# LvlTranslate.net
KiCad netlist of a schematic drawn in Altium Designer
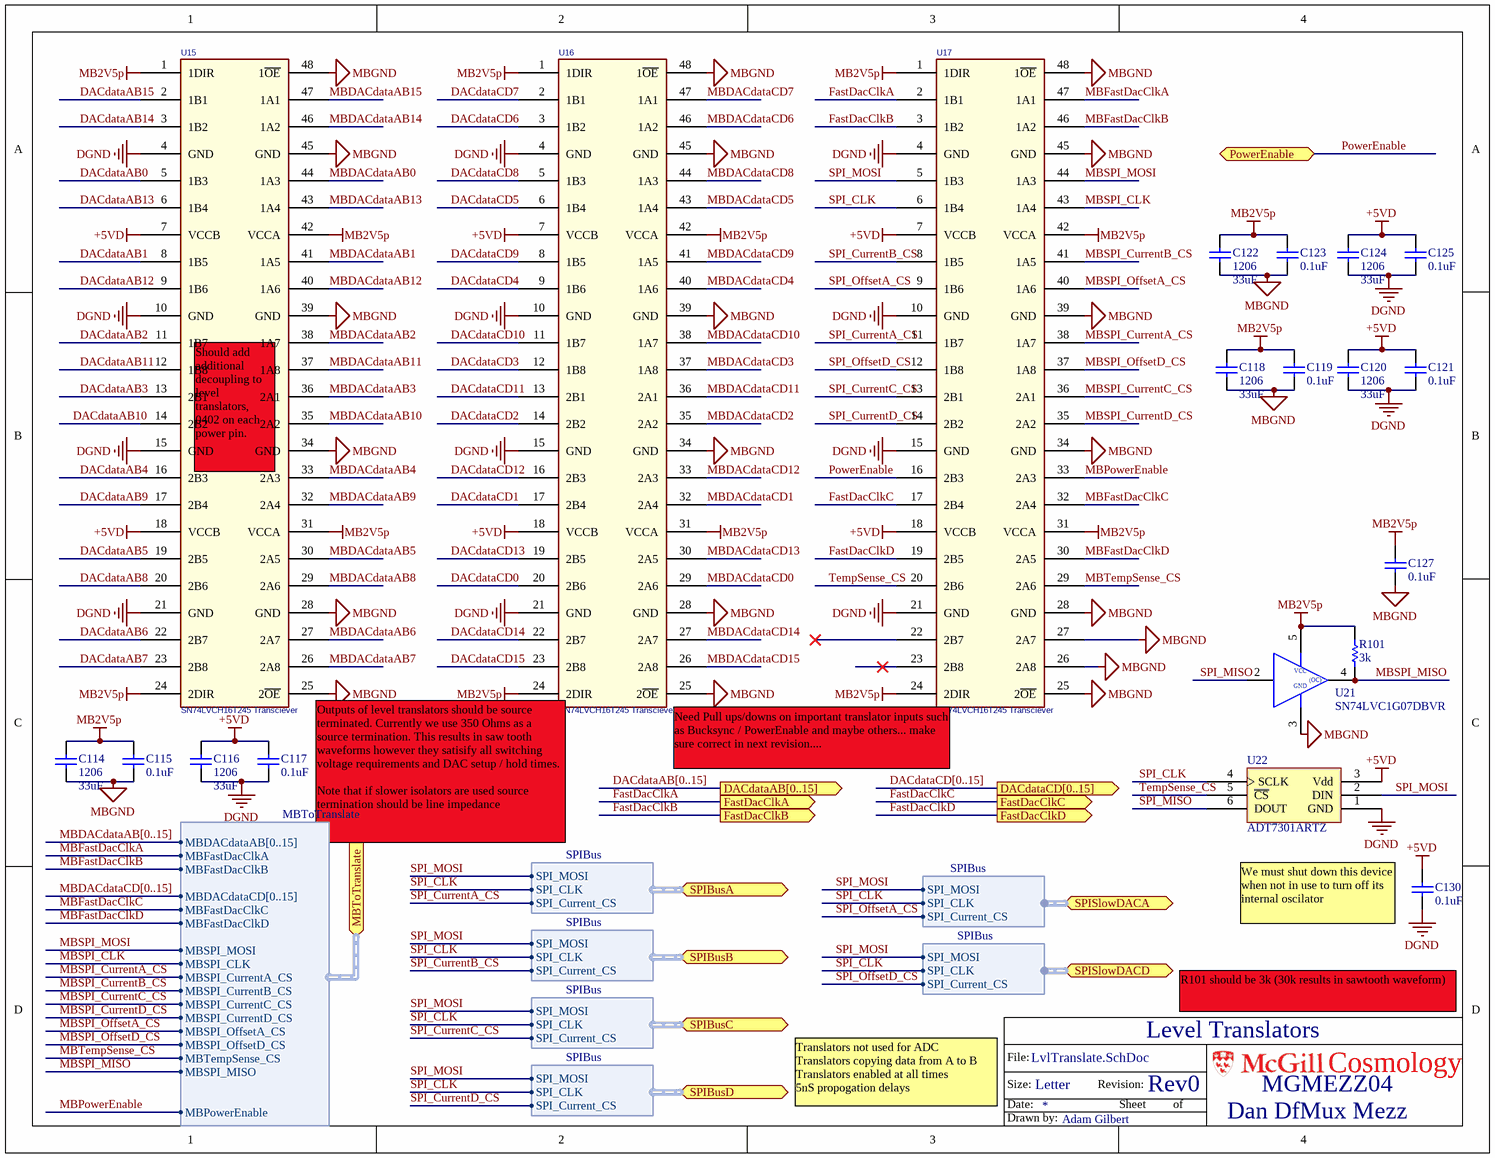
[diagram p0: LvlTranslate.SchDoc]

(export (version "E")
  (design (tool "Eeschema 10.0.6"))
  (components
    (comp (ref "C114")
      (value "33uF")
      (footprint "1206")
      (description "Capacitor, Ceramic, 1210")
      (fields
        (field (name "MANUFACTURER") "TDK Corporation")
        (field (name "MANUFACTURERS PART NUMBER") "C3216X5R1E336M")
      )
      (libsource (lib "MGMEZZ04") (part "CAP 1210"))
    )
    (comp (ref "C115")
      (value "0.1uF")
      (footprint "0603")
      (description "Capacitor, Ceramic, 0603")
      (fields (field (name "MANUFACTURER") "Generic"))
      (libsource (lib "MGMEZZ04") (part "CAP 0603"))
    )
    (comp (ref "C116")
      (value "33uF")
      (footprint "1206")
      (description "Capacitor, Ceramic, 1210")
      (fields
        (field (name "MANUFACTURER") "TDK Corporation")
        (field (name "MANUFACTURERS PART NUMBER") "C3216X5R1E336M")
      )
      (libsource (lib "MGMEZZ04") (part "CAP 1210"))
    )
    (comp (ref "C117")
      (value "0.1uF")
      (footprint "0603")
      (description "Capacitor, Ceramic, 0603")
      (fields (field (name "MANUFACTURER") "Generic"))
      (libsource (lib "MGMEZZ04") (part "CAP 0603"))
    )
    (comp (ref "C118")
      (value "33uF")
      (footprint "1206")
      (description "Capacitor, Ceramic, 1210")
      (fields
        (field (name "MANUFACTURER") "TDK Corporation")
        (field (name "MANUFACTURERS PART NUMBER") "C3216X5R1E336M")
      )
      (libsource (lib "MGMEZZ04") (part "CAP 1210"))
    )
    (comp (ref "C119")
      (value "0.1uF")
      (footprint "0603")
      (description "Capacitor, Ceramic, 0603")
      (fields (field (name "MANUFACTURER") "Generic"))
      (libsource (lib "MGMEZZ04") (part "CAP 0603"))
    )
    (comp (ref "C120")
      (value "33uF")
      (footprint "1206")
      (description "Capacitor, Ceramic, 1210")
      (fields
        (field (name "MANUFACTURER") "TDK Corporation")
        (field (name "MANUFACTURERS PART NUMBER") "C3216X5R1E336M")
      )
      (libsource (lib "MGMEZZ04") (part "CAP 1210"))
    )
    (comp (ref "C121")
      (value "0.1uF")
      (footprint "0603")
      (description "Capacitor, Ceramic, 0603")
      (fields (field (name "MANUFACTURER") "Generic"))
      (libsource (lib "MGMEZZ04") (part "CAP 0603"))
    )
    (comp (ref "C122")
      (value "33uF")
      (footprint "1206")
      (description "Capacitor, Ceramic, 1210")
      (fields
        (field (name "MANUFACTURER") "TDK Corporation")
        (field (name "MANUFACTURERS PART NUMBER") "C3216X5R1E336M")
      )
      (libsource (lib "MGMEZZ04") (part "CAP 1210"))
    )
    (comp (ref "C123")
      (value "0.1uF")
      (footprint "0603")
      (description "Capacitor, Ceramic, 0603")
      (fields (field (name "MANUFACTURER") "Generic"))
      (libsource (lib "MGMEZZ04") (part "CAP 0603"))
    )
    (comp (ref "C124")
      (value "33uF")
      (footprint "1206")
      (description "Capacitor, Ceramic, 1210")
      (fields
        (field (name "MANUFACTURER") "TDK Corporation")
        (field (name "MANUFACTURERS PART NUMBER") "C3216X5R1E336M")
      )
      (libsource (lib "MGMEZZ04") (part "CAP 1210"))
    )
    (comp (ref "C125")
      (value "0.1uF")
      (footprint "0603")
      (description "Capacitor, Ceramic, 0603")
      (fields (field (name "MANUFACTURER") "Generic"))
      (libsource (lib "MGMEZZ04") (part "CAP 0603"))
    )
    (comp (ref "C127")
      (value "0.1uF")
      (footprint "0603")
      (description "Capacitor, Ceramic, 0603")
      (fields (field (name "MANUFACTURER") "Generic"))
      (libsource (lib "MGMEZZ04") (part "CAP 0603"))
    )
    (comp (ref "C130")
      (value "0.1uF")
      (footprint "0603")
      (description "Capacitor, Ceramic, 0603")
      (fields (field (name "MANUFACTURER") "Generic"))
      (libsource (lib "MGMEZZ04") (part "CAP 0603"))
    )
    (comp (ref "R101")
      (value "3k")
      (footprint "0603")
      (description "Resistor")
      (fields (field (name "MANUFACTURER") "Generic"))
      (libsource (lib "MGMEZZ04") (part "RES 0603"))
    )
    (comp (ref "U15")
      (value "SN74LVCH16T245 Transciever")
      (footprint "TSSOP48-0.5mmpitch")
      (fields
        (field (name "MANUFACTURER") "Texas Instruments")
        (field (name "MANUFACTURERS PART NUMBER") "SN74LVCH16T245")
      )
      (libsource (lib "MGMEZZ04") (part "SN74LVCH16T245 Transciever"))
    )
    (comp (ref "U16")
      (value "SN74LVCH16T245 Transciever")
      (footprint "TSSOP48-0.5mmpitch")
      (fields
        (field (name "MANUFACTURER") "Texas Instruments")
        (field (name "MANUFACTURERS PART NUMBER") "SN74LVCH16T245")
      )
      (libsource (lib "MGMEZZ04") (part "SN74LVCH16T245 Transciever"))
    )
    (comp (ref "U17")
      (value "SN74LVCH16T245 Transciever")
      (footprint "TSSOP48-0.5mmpitch")
      (fields
        (field (name "MANUFACTURER") "Texas Instruments")
        (field (name "MANUFACTURERS PART NUMBER") "SN74LVCH16T245")
      )
      (libsource (lib "MGMEZZ04") (part "SN74LVCH16T245 Transciever"))
    )
    (comp (ref "U21")
      (value "74LVC1G07")
      (footprint "SOT23-5")
      (description "Single  NON-INVERTING BUFFER, Open Drain")
      (fields
        (field (name "MANUFACTURER") "Texas Instruments")
        (field (name "MANUFACTURERS PART NUMBER") "SN74LVC1G07DBVR")
      )
      (libsource (lib "MGMEZZ04") (part "74LVC1G07"))
    )
    (comp (ref "U22")
      (value "ADT7301ARTZ")
      (footprint "SOT23-6")
      (description "Digital Temperature Sensor, 13-Bit, +/-1 Degree Accurate")
      (fields (field (name "MANUFACTURER") "Analog Devices"))
      (libsource (lib "ADCMezz3") (part "ADT7301"))
    )
  )
  (nets
    (net (code "3") (name "+5VD") (class "Default")
      (node (ref "C116") (pin "1") (pinfunction "1_1") (pintype "passive"))
      (node (ref "C117") (pin "1") (pinfunction "1_1") (pintype "passive"))
      (node (ref "C120") (pin "1") (pinfunction "1_1") (pintype "passive"))
      (node (ref "C121") (pin "1") (pinfunction "1_1") (pintype "passive"))
      (node (ref "C124") (pin "1") (pinfunction "1_1") (pintype "passive"))
      (node (ref "C125") (pin "1") (pinfunction "1_1") (pintype "passive"))
      (node (ref "C130") (pin "1") (pinfunction "1_1") (pintype "passive"))
      (node (ref "U15") (pin "18") (pinfunction "VCCB_18") (pintype "passive"))
      (node (ref "U15") (pin "7") (pinfunction "VCCB_7") (pintype "passive"))
      (node (ref "U16") (pin "18") (pinfunction "VCCB_18") (pintype "passive"))
      (node (ref "U16") (pin "7") (pinfunction "VCCB_7") (pintype "passive"))
      (node (ref "U17") (pin "18") (pinfunction "VCCB_18") (pintype "passive"))
      (node (ref "U17") (pin "7") (pinfunction "VCCB_7") (pintype "passive"))
      (node (ref "U22") (pin "3") (pinfunction "Vdd_3") (pintype "power_in"))
    )
    (net (code "4") (name "/DACdataAB0") (class "Default")
      (node (ref "U15") (pin "5") (pinfunction "1B3_5") (pintype "passive"))
    )
    (net (code "5") (name "/DACdataAB1") (class "Default")
      (node (ref "U15") (pin "8") (pinfunction "1B5_8") (pintype "passive"))
    )
    (net (code "6") (name "/DACdataAB2") (class "Default")
      (node (ref "U15") (pin "11") (pinfunction "1B7_11") (pintype "passive"))
    )
    (net (code "7") (name "/DACdataAB3") (class "Default")
      (node (ref "U15") (pin "13") (pinfunction "2B1_13") (pintype "passive"))
    )
    (net (code "8") (name "/DACdataAB4") (class "Default")
      (node (ref "U15") (pin "16") (pinfunction "2B3_16") (pintype "passive"))
    )
    (net (code "9") (name "/DACdataAB5") (class "Default")
      (node (ref "U15") (pin "19") (pinfunction "2B5_19") (pintype "passive"))
    )
    (net (code "10") (name "/DACdataAB6") (class "Default")
      (node (ref "U15") (pin "22") (pinfunction "2B7_22") (pintype "passive"))
    )
    (net (code "11") (name "/DACdataAB7") (class "Default")
      (node (ref "U15") (pin "23") (pinfunction "2B8_23") (pintype "passive"))
    )
    (net (code "12") (name "/DACdataAB8") (class "Default")
      (node (ref "U15") (pin "20") (pinfunction "2B6_20") (pintype "passive"))
    )
    (net (code "13") (name "/DACdataAB9") (class "Default")
      (node (ref "U15") (pin "17") (pinfunction "2B4_17") (pintype "passive"))
    )
    (net (code "14") (name "/DACdataAB10") (class "Default")
      (node (ref "U15") (pin "14") (pinfunction "2B2_14") (pintype "passive"))
    )
    (net (code "15") (name "/DACdataAB11") (class "Default")
      (node (ref "U15") (pin "12") (pinfunction "1B8_12") (pintype "passive"))
    )
    (net (code "16") (name "/DACdataAB12") (class "Default")
      (node (ref "U15") (pin "9") (pinfunction "1B6_9") (pintype "passive"))
    )
    (net (code "17") (name "/DACdataAB13") (class "Default")
      (node (ref "U15") (pin "6") (pinfunction "1B4_6") (pintype "passive"))
    )
    (net (code "18") (name "/DACdataAB14") (class "Default")
      (node (ref "U15") (pin "3") (pinfunction "1B2_3") (pintype "passive"))
    )
    (net (code "19") (name "/DACdataAB15") (class "Default")
      (node (ref "U15") (pin "2") (pinfunction "1B1_2") (pintype "passive"))
    )
    (net (code "21") (name "/DACdataCD0") (class "Default")
      (node (ref "U16") (pin "20") (pinfunction "2B6_20") (pintype "passive"))
    )
    (net (code "22") (name "/DACdataCD1") (class "Default")
      (node (ref "U16") (pin "17") (pinfunction "2B4_17") (pintype "passive"))
    )
    (net (code "23") (name "/DACdataCD2") (class "Default")
      (node (ref "U16") (pin "14") (pinfunction "2B2_14") (pintype "passive"))
    )
    (net (code "24") (name "/DACdataCD3") (class "Default")
      (node (ref "U16") (pin "12") (pinfunction "1B8_12") (pintype "passive"))
    )
    (net (code "25") (name "/DACdataCD4") (class "Default")
      (node (ref "U16") (pin "9") (pinfunction "1B6_9") (pintype "passive"))
    )
    (net (code "26") (name "/DACdataCD5") (class "Default")
      (node (ref "U16") (pin "6") (pinfunction "1B4_6") (pintype "passive"))
    )
    (net (code "27") (name "/DACdataCD6") (class "Default")
      (node (ref "U16") (pin "3") (pinfunction "1B2_3") (pintype "passive"))
    )
    (net (code "28") (name "/DACdataCD7") (class "Default")
      (node (ref "U16") (pin "2") (pinfunction "1B1_2") (pintype "passive"))
    )
    (net (code "29") (name "/DACdataCD8") (class "Default")
      (node (ref "U16") (pin "5") (pinfunction "1B3_5") (pintype "passive"))
    )
    (net (code "30") (name "/DACdataCD9") (class "Default")
      (node (ref "U16") (pin "8") (pinfunction "1B5_8") (pintype "passive"))
    )
    (net (code "31") (name "/DACdataCD10") (class "Default")
      (node (ref "U16") (pin "11") (pinfunction "1B7_11") (pintype "passive"))
    )
    (net (code "32") (name "/DACdataCD11") (class "Default")
      (node (ref "U16") (pin "13") (pinfunction "2B1_13") (pintype "passive"))
    )
    (net (code "33") (name "/DACdataCD12") (class "Default")
      (node (ref "U16") (pin "16") (pinfunction "2B3_16") (pintype "passive"))
    )
    (net (code "34") (name "/DACdataCD13") (class "Default")
      (node (ref "U16") (pin "19") (pinfunction "2B5_19") (pintype "passive"))
    )
    (net (code "35") (name "/DACdataCD14") (class "Default")
      (node (ref "U16") (pin "22") (pinfunction "2B7_22") (pintype "passive"))
    )
    (net (code "36") (name "/DACdataCD15") (class "Default")
      (node (ref "U16") (pin "23") (pinfunction "2B8_23") (pintype "passive"))
    )
    (net (code "38") (name "/FastDacClkA") (class "Default")
      (node (ref "U17") (pin "2") (pinfunction "1B1_2") (pintype "passive"))
    )
    (net (code "39") (name "/FastDacClkB") (class "Default")
      (node (ref "U17") (pin "3") (pinfunction "1B2_3") (pintype "passive"))
    )
    (net (code "40") (name "/FastDacClkC") (class "Default")
      (node (ref "U17") (pin "17") (pinfunction "2B4_17") (pintype "passive"))
    )
    (net (code "41") (name "/FastDacClkD") (class "Default")
      (node (ref "U17") (pin "19") (pinfunction "2B5_19") (pintype "passive"))
    )
    (net (code "42") (name "/MBDACdataAB0") (class "Default")
      (node (ref "U15") (pin "44") (pinfunction "1A3_44") (pintype "passive"))
    )
    (net (code "43") (name "/MBDACdataAB1") (class "Default")
      (node (ref "U15") (pin "41") (pinfunction "1A5_41") (pintype "passive"))
    )
    (net (code "44") (name "/MBDACdataAB2") (class "Default")
      (node (ref "U15") (pin "38") (pinfunction "1A7_38") (pintype "passive"))
    )
    (net (code "45") (name "/MBDACdataAB3") (class "Default")
      (node (ref "U15") (pin "36") (pinfunction "2A1_36") (pintype "passive"))
    )
    (net (code "46") (name "/MBDACdataAB4") (class "Default")
      (node (ref "U15") (pin "33") (pinfunction "2A3_33") (pintype "passive"))
    )
    (net (code "47") (name "/MBDACdataAB5") (class "Default")
      (node (ref "U15") (pin "30") (pinfunction "2A5_30") (pintype "passive"))
    )
    (net (code "48") (name "/MBDACdataAB6") (class "Default")
      (node (ref "U15") (pin "27") (pinfunction "2A7_27") (pintype "passive"))
    )
    (net (code "49") (name "/MBDACdataAB7") (class "Default")
      (node (ref "U15") (pin "26") (pinfunction "2A8_26") (pintype "passive"))
    )
    (net (code "50") (name "/MBDACdataAB8") (class "Default")
      (node (ref "U15") (pin "29") (pinfunction "2A6_29") (pintype "passive"))
    )
    (net (code "51") (name "/MBDACdataAB9") (class "Default")
      (node (ref "U15") (pin "32") (pinfunction "2A4_32") (pintype "passive"))
    )
    (net (code "52") (name "/MBDACdataAB10") (class "Default")
      (node (ref "U15") (pin "35") (pinfunction "2A2_35") (pintype "passive"))
    )
    (net (code "53") (name "/MBDACdataAB11") (class "Default")
      (node (ref "U15") (pin "37") (pinfunction "1A8_37") (pintype "passive"))
    )
    (net (code "54") (name "/MBDACdataAB12") (class "Default")
      (node (ref "U15") (pin "40") (pinfunction "1A6_40") (pintype "passive"))
    )
    (net (code "55") (name "/MBDACdataAB13") (class "Default")
      (node (ref "U15") (pin "43") (pinfunction "1A4_43") (pintype "passive"))
    )
    (net (code "56") (name "/MBDACdataAB14") (class "Default")
      (node (ref "U15") (pin "46") (pinfunction "1A2_46") (pintype "passive"))
    )
    (net (code "57") (name "/MBDACdataAB15") (class "Default")
      (node (ref "U15") (pin "47") (pinfunction "1A1_47") (pintype "passive"))
    )
    (net (code "59") (name "/MBDACdataCD0") (class "Default")
      (node (ref "U16") (pin "29") (pinfunction "2A6_29") (pintype "passive"))
    )
    (net (code "60") (name "/MBDACdataCD1") (class "Default")
      (node (ref "U16") (pin "32") (pinfunction "2A4_32") (pintype "passive"))
    )
    (net (code "61") (name "/MBDACdataCD2") (class "Default")
      (node (ref "U16") (pin "35") (pinfunction "2A2_35") (pintype "passive"))
    )
    (net (code "62") (name "/MBDACdataCD3") (class "Default")
      (node (ref "U16") (pin "37") (pinfunction "1A8_37") (pintype "passive"))
    )
    (net (code "63") (name "/MBDACdataCD4") (class "Default")
      (node (ref "U16") (pin "40") (pinfunction "1A6_40") (pintype "passive"))
    )
    (net (code "64") (name "/MBDACdataCD5") (class "Default")
      (node (ref "U16") (pin "43") (pinfunction "1A4_43") (pintype "passive"))
    )
    (net (code "65") (name "/MBDACdataCD6") (class "Default")
      (node (ref "U16") (pin "46") (pinfunction "1A2_46") (pintype "passive"))
    )
    (net (code "66") (name "/MBDACdataCD7") (class "Default")
      (node (ref "U16") (pin "47") (pinfunction "1A1_47") (pintype "passive"))
    )
    (net (code "67") (name "/MBDACdataCD8") (class "Default")
      (node (ref "U16") (pin "44") (pinfunction "1A3_44") (pintype "passive"))
    )
    (net (code "68") (name "/MBDACdataCD9") (class "Default")
      (node (ref "U16") (pin "41") (pinfunction "1A5_41") (pintype "passive"))
    )
    (net (code "69") (name "/MBDACdataCD10") (class "Default")
      (node (ref "U16") (pin "38") (pinfunction "1A7_38") (pintype "passive"))
    )
    (net (code "70") (name "/MBDACdataCD11") (class "Default")
      (node (ref "U16") (pin "36") (pinfunction "2A1_36") (pintype "passive"))
    )
    (net (code "71") (name "/MBDACdataCD12") (class "Default")
      (node (ref "U16") (pin "33") (pinfunction "2A3_33") (pintype "passive"))
    )
    (net (code "72") (name "/MBDACdataCD13") (class "Default")
      (node (ref "U16") (pin "30") (pinfunction "2A5_30") (pintype "passive"))
    )
    (net (code "73") (name "/MBDACdataCD14") (class "Default")
      (node (ref "U16") (pin "27") (pinfunction "2A7_27") (pintype "passive"))
    )
    (net (code "74") (name "/MBDACdataCD15") (class "Default")
      (node (ref "U16") (pin "26") (pinfunction "2A8_26") (pintype "passive"))
    )
    (net (code "76") (name "/MBFastDacClkA") (class "Default")
      (node (ref "U17") (pin "47") (pinfunction "1A1_47") (pintype "passive"))
    )
    (net (code "77") (name "/MBFastDacClkB") (class "Default")
      (node (ref "U17") (pin "46") (pinfunction "1A2_46") (pintype "passive"))
    )
    (net (code "78") (name "/MBFastDacClkC") (class "Default")
      (node (ref "U17") (pin "32") (pinfunction "2A4_32") (pintype "passive"))
    )
    (net (code "79") (name "/MBFastDacClkD") (class "Default")
      (node (ref "U17") (pin "30") (pinfunction "2A5_30") (pintype "passive"))
    )
    (net (code "80") (name "/MBPowerEnable") (class "Default")
      (node (ref "U17") (pin "33") (pinfunction "2A3_33") (pintype "passive"))
    )
    (net (code "81") (name "/MBSPI_CLK") (class "Default")
      (node (ref "U17") (pin "43") (pinfunction "1A4_43") (pintype "passive"))
    )
    (net (code "82") (name "/MBSPI_CurrentA_CS") (class "Default")
      (node (ref "U17") (pin "38") (pinfunction "1A7_38") (pintype "passive"))
    )
    (net (code "83") (name "/MBSPI_CurrentB_CS") (class "Default")
      (node (ref "U17") (pin "41") (pinfunction "1A5_41") (pintype "passive"))
    )
    (net (code "84") (name "/MBSPI_CurrentC_CS") (class "Default")
      (node (ref "U17") (pin "36") (pinfunction "2A1_36") (pintype "passive"))
    )
    (net (code "85") (name "/MBSPI_CurrentD_CS") (class "Default")
      (node (ref "U17") (pin "35") (pinfunction "2A2_35") (pintype "passive"))
    )
    (net (code "86") (name "/MBSPI_MISO") (class "Default")
      (node (ref "R101") (pin "1") (pinfunction "1_1") (pintype "passive"))
      (node (ref "U21") (pin "4") (pinfunction "Y_4") (pintype "passive"))
    )
    (net (code "87") (name "/MBSPI_MOSI") (class "Default")
      (node (ref "U17") (pin "44") (pinfunction "1A3_44") (pintype "passive"))
    )
    (net (code "88") (name "/MBSPI_OffsetA_CS") (class "Default")
      (node (ref "U17") (pin "40") (pinfunction "1A6_40") (pintype "passive"))
    )
    (net (code "89") (name "/MBSPI_OffsetD_CS") (class "Default")
      (node (ref "U17") (pin "37") (pinfunction "1A8_37") (pintype "passive"))
    )
    (net (code "90") (name "/MBTempSense_CS") (class "Default")
      (node (ref "U17") (pin "29") (pinfunction "2A6_29") (pintype "passive"))
    )
    (net (code "91") (name "/PowerEnable") (class "Default")
      (node (ref "U17") (pin "16") (pinfunction "2B3_16") (pintype "passive"))
    )
    (net (code "92") (name "/SPI_CLK") (class "Default")
      (node (ref "U17") (pin "6") (pinfunction "1B4_6") (pintype "passive"))
      (node (ref "U22") (pin "4") (pinfunction "SCLK_4") (pintype "passive"))
    )
    (net (code "93") (name "/SPI_CurrentA_CS") (class "Default")
      (node (ref "U17") (pin "11") (pinfunction "1B7_11") (pintype "passive"))
    )
    (net (code "94") (name "/SPI_CurrentB_CS") (class "Default")
      (node (ref "U17") (pin "8") (pinfunction "1B5_8") (pintype "passive"))
    )
    (net (code "95") (name "/SPI_CurrentC_CS") (class "Default")
      (node (ref "U17") (pin "13") (pinfunction "2B1_13") (pintype "passive"))
    )
    (net (code "96") (name "/SPI_CurrentD_CS") (class "Default")
      (node (ref "U17") (pin "14") (pinfunction "2B2_14") (pintype "passive"))
    )
    (net (code "97") (name "/SPI_MISO") (class "Default")
      (node (ref "U21") (pin "2") (pinfunction "A_2") (pintype "passive"))
      (node (ref "U22") (pin "6") (pinfunction "DOUT_6") (pintype "passive"))
    )
    (net (code "98") (name "/SPI_MOSI") (class "Default")
      (node (ref "U17") (pin "5") (pinfunction "1B3_5") (pintype "passive"))
      (node (ref "U22") (pin "2") (pinfunction "DIN_2") (pintype "passive"))
    )
    (net (code "99") (name "/SPI_OffsetA_CS") (class "Default")
      (node (ref "U17") (pin "9") (pinfunction "1B6_9") (pintype "passive"))
    )
    (net (code "100") (name "/SPI_OffsetD_CS") (class "Default")
      (node (ref "U17") (pin "12") (pinfunction "1B8_12") (pintype "passive"))
    )
    (net (code "101") (name "/TempSense_CS") (class "Default")
      (node (ref "U17") (pin "20") (pinfunction "2B6_20") (pintype "passive"))
      (node (ref "U22") (pin "5") (pinfunction "~{CS}_5") (pintype "passive"))
    )
    (net (code "104") (name "DGND") (class "Default")
      (node (ref "C116") (pin "2") (pinfunction "2_2") (pintype "passive"))
      (node (ref "C117") (pin "2") (pinfunction "2_2") (pintype "passive"))
      (node (ref "C120") (pin "2") (pinfunction "2_2") (pintype "passive"))
      (node (ref "C121") (pin "2") (pinfunction "2_2") (pintype "passive"))
      (node (ref "C124") (pin "2") (pinfunction "2_2") (pintype "passive"))
      (node (ref "C125") (pin "2") (pinfunction "2_2") (pintype "passive"))
      (node (ref "C130") (pin "2") (pinfunction "2_2") (pintype "passive"))
      (node (ref "U15") (pin "10") (pinfunction "GND_10") (pintype "passive"))
      (node (ref "U15") (pin "15") (pinfunction "GND_15") (pintype "passive"))
      (node (ref "U15") (pin "21") (pinfunction "GND_21") (pintype "passive"))
      (node (ref "U15") (pin "4") (pinfunction "GND_4") (pintype "passive"))
      (node (ref "U16") (pin "10") (pinfunction "GND_10") (pintype "passive"))
      (node (ref "U16") (pin "15") (pinfunction "GND_15") (pintype "passive"))
      (node (ref "U16") (pin "21") (pinfunction "GND_21") (pintype "passive"))
      (node (ref "U16") (pin "4") (pinfunction "GND_4") (pintype "passive"))
      (node (ref "U17") (pin "10") (pinfunction "GND_10") (pintype "passive"))
      (node (ref "U17") (pin "15") (pinfunction "GND_15") (pintype "passive"))
      (node (ref "U17") (pin "21") (pinfunction "GND_21") (pintype "passive"))
      (node (ref "U17") (pin "4") (pinfunction "GND_4") (pintype "passive"))
      (node (ref "U22") (pin "1") (pinfunction "GND_1") (pintype "power_in"))
    )
    (net (code "105") (name "MB2V5p") (class "Default")
      (node (ref "C114") (pin "1") (pinfunction "1_1") (pintype "passive"))
      (node (ref "C115") (pin "1") (pinfunction "1_1") (pintype "passive"))
      (node (ref "C118") (pin "1") (pinfunction "1_1") (pintype "passive"))
      (node (ref "C119") (pin "1") (pinfunction "1_1") (pintype "passive"))
      (node (ref "C122") (pin "1") (pinfunction "1_1") (pintype "passive"))
      (node (ref "C123") (pin "1") (pinfunction "1_1") (pintype "passive"))
      (node (ref "C127") (pin "1") (pinfunction "1_1") (pintype "passive"))
      (node (ref "R101") (pin "2") (pinfunction "2_2") (pintype "passive"))
      (node (ref "U15") (pin "1") (pinfunction "1DIR_1") (pintype "passive"))
      (node (ref "U15") (pin "24") (pinfunction "2DIR_24") (pintype "passive"))
      (node (ref "U15") (pin "31") (pinfunction "VCCA_31") (pintype "passive"))
      (node (ref "U15") (pin "42") (pinfunction "VCCA_42") (pintype "passive"))
      (node (ref "U16") (pin "1") (pinfunction "1DIR_1") (pintype "passive"))
      (node (ref "U16") (pin "24") (pinfunction "2DIR_24") (pintype "passive"))
      (node (ref "U16") (pin "31") (pinfunction "VCCA_31") (pintype "passive"))
      (node (ref "U16") (pin "42") (pinfunction "VCCA_42") (pintype "passive"))
      (node (ref "U17") (pin "1") (pinfunction "1DIR_1") (pintype "passive"))
      (node (ref "U17") (pin "24") (pinfunction "2DIR_24") (pintype "passive"))
      (node (ref "U17") (pin "31") (pinfunction "VCCA_31") (pintype "passive"))
      (node (ref "U17") (pin "42") (pinfunction "VCCA_42") (pintype "passive"))
      (node (ref "U21") (pin "5") (pinfunction "Vcc_5") (pintype "power_in"))
    )
    (net (code "106") (name "MBGND") (class "Default")
      (node (ref "C114") (pin "2") (pinfunction "2_2") (pintype "passive"))
      (node (ref "C115") (pin "2") (pinfunction "2_2") (pintype "passive"))
      (node (ref "C118") (pin "2") (pinfunction "2_2") (pintype "passive"))
      (node (ref "C119") (pin "2") (pinfunction "2_2") (pintype "passive"))
      (node (ref "C122") (pin "2") (pinfunction "2_2") (pintype "passive"))
      (node (ref "C123") (pin "2") (pinfunction "2_2") (pintype "passive"))
      (node (ref "C127") (pin "2") (pinfunction "2_2") (pintype "passive"))
      (node (ref "U15") (pin "25") (pinfunction "2~{OE}_25") (pintype "passive"))
      (node (ref "U15") (pin "28") (pinfunction "GND_28") (pintype "passive"))
      (node (ref "U15") (pin "34") (pinfunction "GND_34") (pintype "passive"))
      (node (ref "U15") (pin "39") (pinfunction "GND_39") (pintype "passive"))
      (node (ref "U15") (pin "45") (pinfunction "GND_45") (pintype "passive"))
      (node (ref "U15") (pin "48") (pinfunction "1~{OE}_48") (pintype "passive"))
      (node (ref "U16") (pin "25") (pinfunction "2~{OE}_25") (pintype "passive"))
      (node (ref "U16") (pin "28") (pinfunction "GND_28") (pintype "passive"))
      (node (ref "U16") (pin "34") (pinfunction "GND_34") (pintype "passive"))
      (node (ref "U16") (pin "39") (pinfunction "GND_39") (pintype "passive"))
      (node (ref "U16") (pin "45") (pinfunction "GND_45") (pintype "passive"))
      (node (ref "U16") (pin "48") (pinfunction "1~{OE}_48") (pintype "passive"))
      (node (ref "U17") (pin "25") (pinfunction "2~{OE}_25") (pintype "passive"))
      (node (ref "U17") (pin "26") (pinfunction "2A8_26") (pintype "passive"))
      (node (ref "U17") (pin "27") (pinfunction "2A7_27") (pintype "passive"))
      (node (ref "U17") (pin "28") (pinfunction "GND_28") (pintype "passive"))
      (node (ref "U17") (pin "34") (pinfunction "GND_34") (pintype "passive"))
      (node (ref "U17") (pin "39") (pinfunction "GND_39") (pintype "passive"))
      (node (ref "U17") (pin "45") (pinfunction "GND_45") (pintype "passive"))
      (node (ref "U17") (pin "48") (pinfunction "1~{OE}_48") (pintype "passive"))
      (node (ref "U21") (pin "3") (pinfunction "Gnd_3") (pintype "power_in"))
    )
    (net (code "107") (name "unconnected-(U17-2B7-Pad22)") (class "Default")
      (node (ref "U17") (pin "22") (pinfunction "2B7_22") (pintype "passive+no_connect"))
    )
    (net (code "108") (name "unconnected-(U17-2B8-Pad23)") (class "Default")
      (node (ref "U17") (pin "23") (pinfunction "2B8_23") (pintype "passive"))
    )
  )
)
